# 1-Schematic_Remote1000.net
KiCad netlist of a schematic drawn in EasyEDA
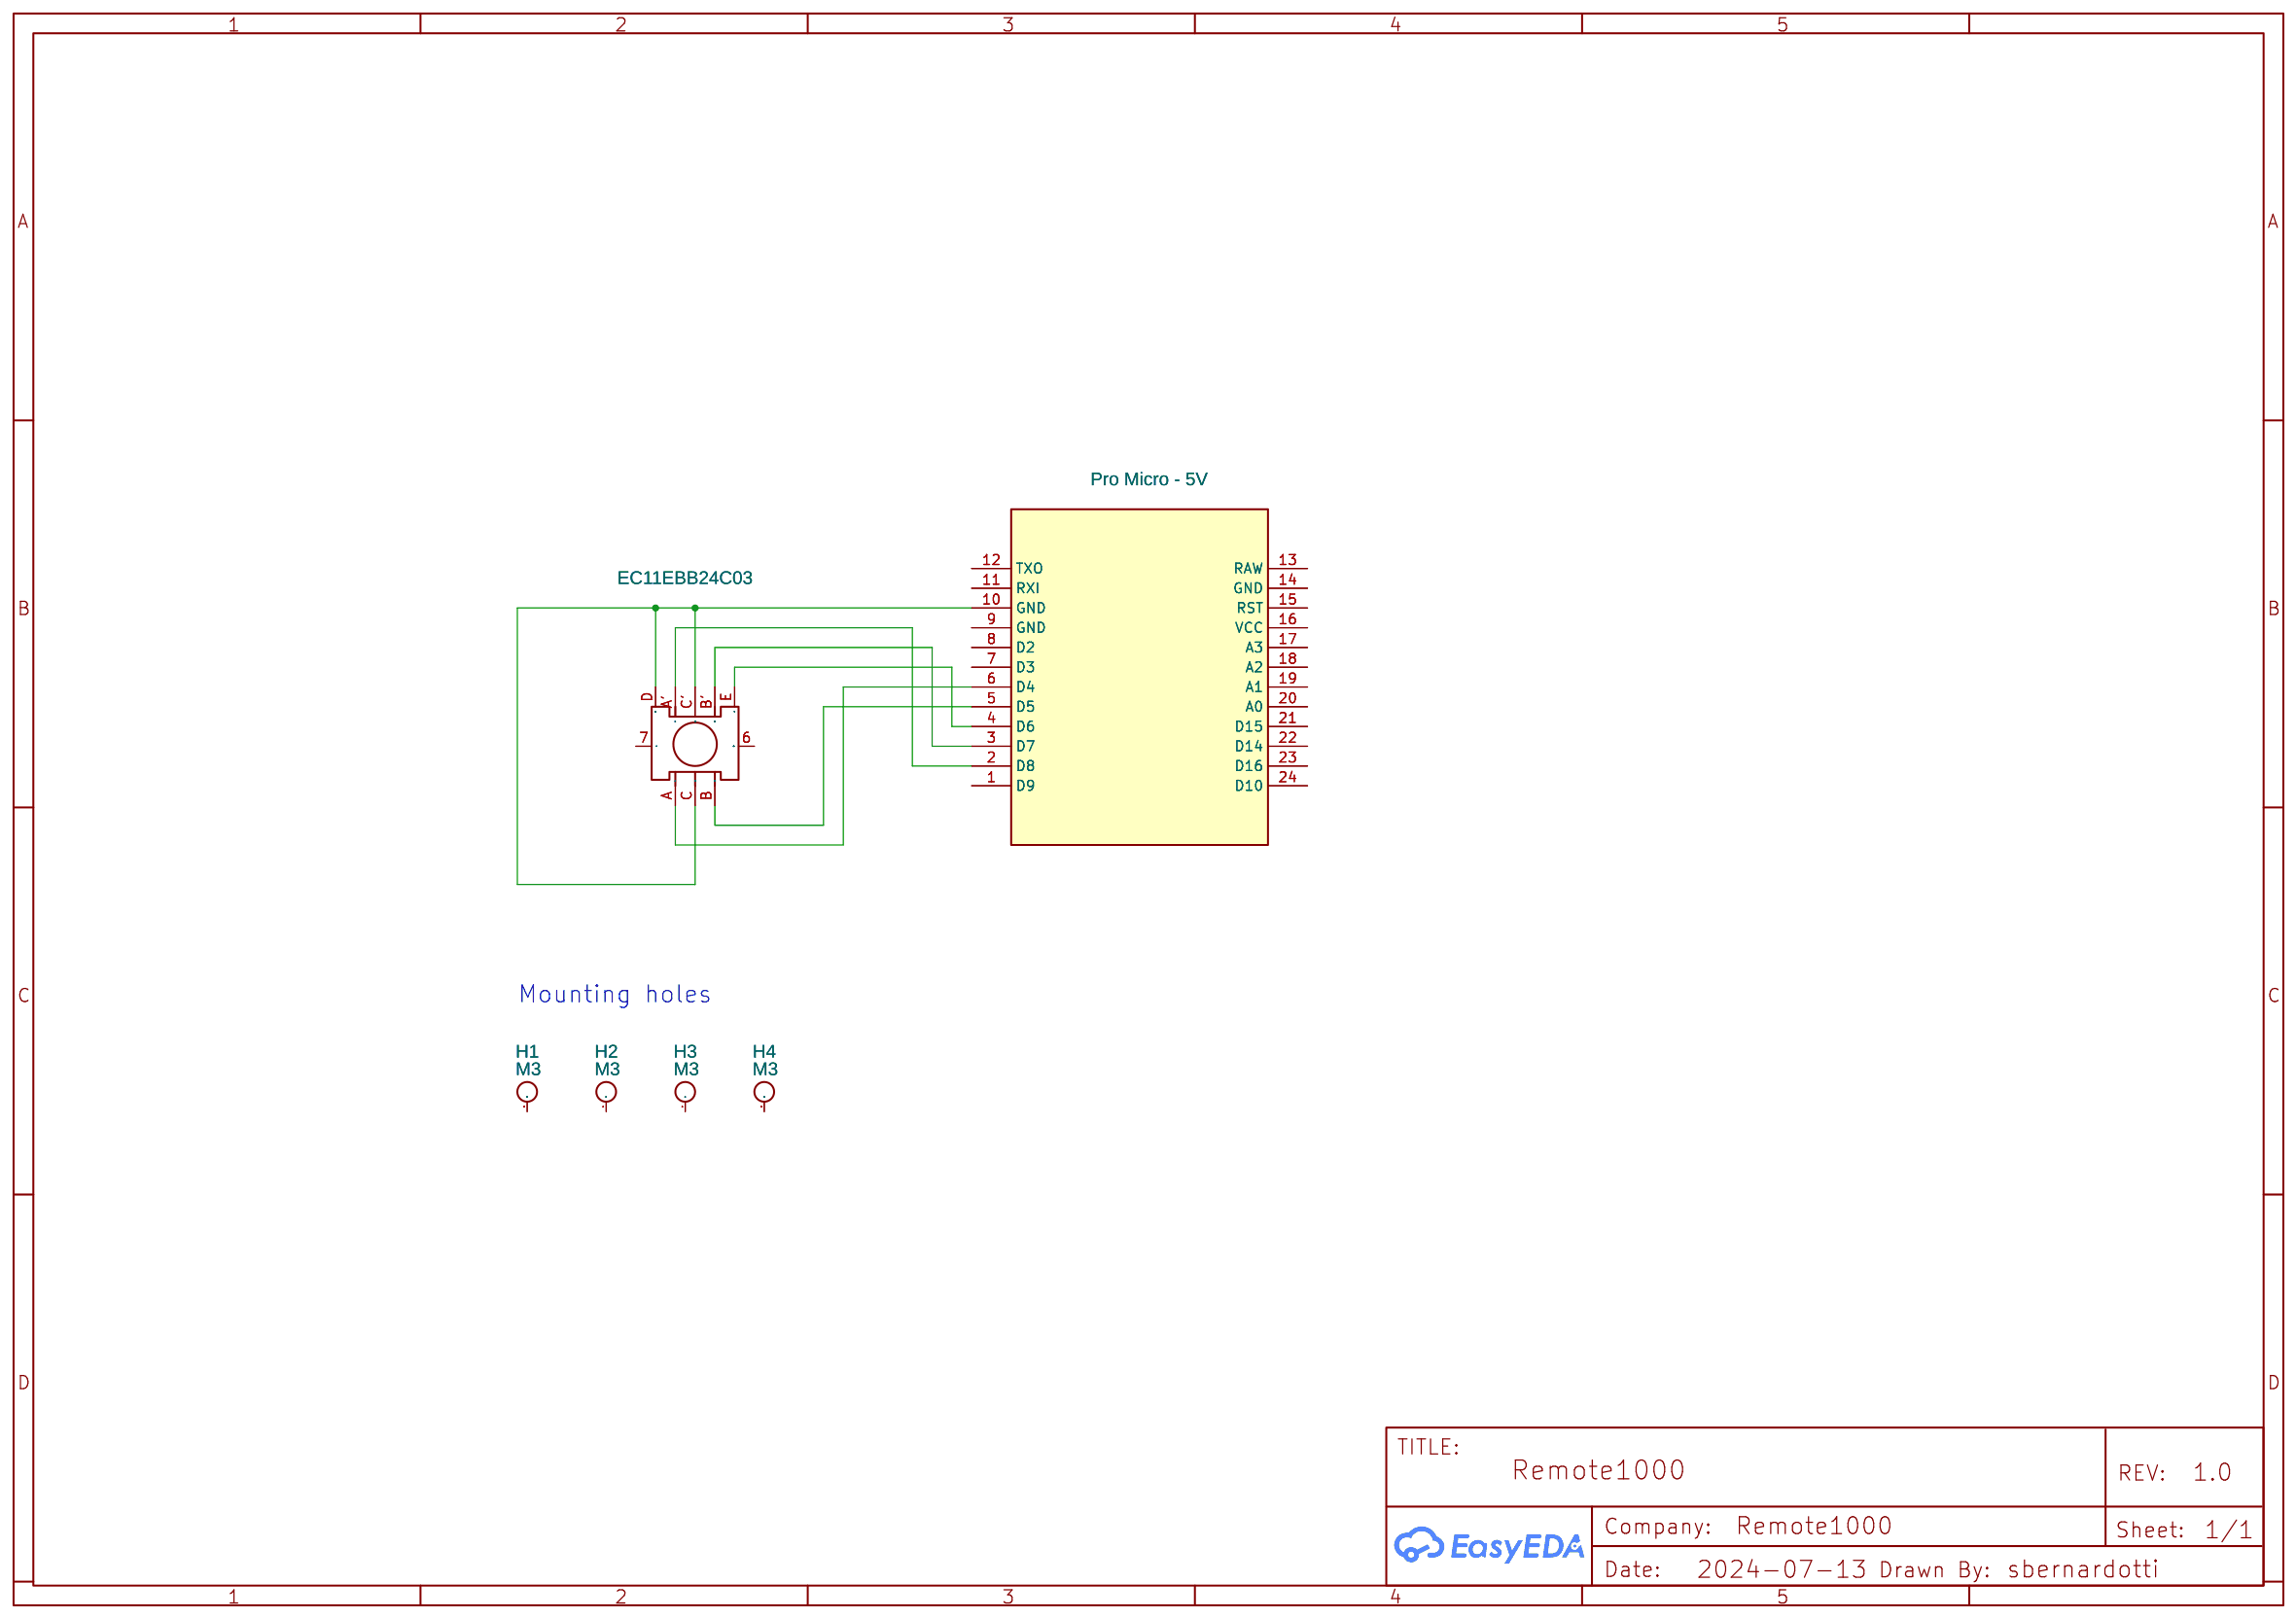
[diagram p0: schematic sheet]

(export (version "E")
  (design (tool "Eeschema 10.0.6"))
  (components
    (comp (ref "H1") (value "M3") (libsource (lib "") (part "HOLE_D3M5_D7M0_PCB_MOUNTING")))
    (comp (ref "H2") (value "M3") (libsource (lib "") (part "HOLE_D3M5_D7M0_PCB_MOUNTING")))
    (comp (ref "H3") (value "M3") (libsource (lib "") (part "HOLE_D3M5_D7M0_PCB_MOUNTING")))
    (comp (ref "H4") (value "M3") (libsource (lib "") (part "HOLE_D3M5_D7M0_PCB_MOUNTING")))
    (comp (ref "P1") (value "Pro Micro - 5V") (libsource (lib "") (part "Pro Micro - 5V")))
    (comp (ref "SW1")
      (value "EC11EBB24C03")
      (fields (field (name "Manufacturer") "ALPSALPINE(阿尔卑斯阿尔派)"))
      (libsource (lib "") (part "EC11EBB24C03"))
    )
  )
  (nets
    (net (code "1") (name "Net-(P1-D4)") (class "Default")
      (node (ref "P1") (pin "6") (pinfunction "D4_6") (pintype "unspecified"))
      (node (ref "SW1") (pin "A") (pinfunction "A_A") (pintype "unspecified"))
    )
    (net (code "2") (name "Net-(P1-D5)") (class "Default")
      (node (ref "P1") (pin "5") (pinfunction "D5_5") (pintype "unspecified"))
      (node (ref "SW1") (pin "B") (pinfunction "B_B") (pintype "unspecified"))
    )
    (net (code "3") (name "Net-(P1-D6)") (class "Default")
      (node (ref "P1") (pin "4") (pinfunction "D6_4") (pintype "unspecified"))
      (node (ref "SW1") (pin "E") (pinfunction "E_E") (pintype "unspecified"))
    )
    (net (code "4") (name "Net-(P1-D7)") (class "Default")
      (node (ref "P1") (pin "3") (pinfunction "D7_3") (pintype "unspecified"))
      (node (ref "SW1") (pin "B'") (pinfunction "B'_B'") (pintype "unspecified"))
    )
    (net (code "5") (name "Net-(P1-D8)") (class "Default")
      (node (ref "P1") (pin "2") (pinfunction "D8_2") (pintype "unspecified"))
      (node (ref "SW1") (pin "A'") (pinfunction "A'_A'") (pintype "unspecified"))
    )
    (net (code "6") (name "Net-(P1-GND-Pad10)") (class "Default")
      (node (ref "P1") (pin "10") (pinfunction "GND_10") (pintype "unspecified"))
      (node (ref "SW1") (pin "C") (pinfunction "C_C") (pintype "unspecified"))
      (node (ref "SW1") (pin "C'") (pinfunction "C'_C'") (pintype "unspecified"))
      (node (ref "SW1") (pin "D") (pinfunction "D_D") (pintype "unspecified"))
    )
    (net (code "7") (name "unconnected-(H1-Pad1)") (class "Default")
      (node (ref "H1") (pin "1") (pinfunction "1_1") (pintype "unspecified"))
    )
    (net (code "8") (name "unconnected-(H2-Pad1)") (class "Default")
      (node (ref "H2") (pin "1") (pinfunction "1_1") (pintype "unspecified"))
    )
    (net (code "9") (name "unconnected-(H3-Pad1)") (class "Default")
      (node (ref "H3") (pin "1") (pinfunction "1_1") (pintype "unspecified"))
    )
    (net (code "10") (name "unconnected-(H4-Pad1)") (class "Default")
      (node (ref "H4") (pin "1") (pinfunction "1_1") (pintype "unspecified"))
    )
    (net (code "11") (name "unconnected-(P1-A0-Pad20)") (class "Default")
      (node (ref "P1") (pin "20") (pinfunction "A0_20") (pintype "unspecified"))
    )
    (net (code "12") (name "unconnected-(P1-A1-Pad19)") (class "Default")
      (node (ref "P1") (pin "19") (pinfunction "A1_19") (pintype "unspecified"))
    )
    (net (code "13") (name "unconnected-(P1-A2-Pad18)") (class "Default")
      (node (ref "P1") (pin "18") (pinfunction "A2_18") (pintype "unspecified"))
    )
    (net (code "14") (name "unconnected-(P1-A3-Pad17)") (class "Default")
      (node (ref "P1") (pin "17") (pinfunction "A3_17") (pintype "unspecified"))
    )
    (net (code "15") (name "unconnected-(P1-D2-Pad8)") (class "Default")
      (node (ref "P1") (pin "8") (pinfunction "D2_8") (pintype "unspecified"))
    )
    (net (code "16") (name "unconnected-(P1-D3-Pad7)") (class "Default")
      (node (ref "P1") (pin "7") (pinfunction "D3_7") (pintype "unspecified"))
    )
    (net (code "17") (name "unconnected-(P1-D9-Pad1)") (class "Default")
      (node (ref "P1") (pin "1") (pinfunction "D9_1") (pintype "unspecified"))
    )
    (net (code "18") (name "unconnected-(P1-D10-Pad24)") (class "Default")
      (node (ref "P1") (pin "24") (pinfunction "D10_24") (pintype "unspecified"))
    )
    (net (code "19") (name "unconnected-(P1-D14-Pad22)") (class "Default")
      (node (ref "P1") (pin "22") (pinfunction "D14_22") (pintype "unspecified"))
    )
    (net (code "20") (name "unconnected-(P1-D15-Pad21)") (class "Default")
      (node (ref "P1") (pin "21") (pinfunction "D15_21") (pintype "unspecified"))
    )
    (net (code "21") (name "unconnected-(P1-D16-Pad23)") (class "Default")
      (node (ref "P1") (pin "23") (pinfunction "D16_23") (pintype "unspecified"))
    )
    (net (code "22") (name "unconnected-(P1-GND-Pad9)") (class "Default")
      (node (ref "P1") (pin "9") (pinfunction "GND_9") (pintype "unspecified"))
    )
    (net (code "23") (name "unconnected-(P1-GND-Pad14)") (class "Default")
      (node (ref "P1") (pin "14") (pinfunction "GND_14") (pintype "unspecified"))
    )
    (net (code "24") (name "unconnected-(P1-RAW-Pad13)") (class "Default")
      (node (ref "P1") (pin "13") (pinfunction "RAW_13") (pintype "unspecified"))
    )
    (net (code "25") (name "unconnected-(P1-RST-Pad15)") (class "Default")
      (node (ref "P1") (pin "15") (pinfunction "RST_15") (pintype "unspecified"))
    )
    (net (code "26") (name "unconnected-(P1-RXI-Pad11)") (class "Default")
      (node (ref "P1") (pin "11") (pinfunction "RXI_11") (pintype "unspecified"))
    )
    (net (code "27") (name "unconnected-(P1-TXO-Pad12)") (class "Default")
      (node (ref "P1") (pin "12") (pinfunction "TXO_12") (pintype "unspecified"))
    )
    (net (code "28") (name "unconnected-(P1-VCC-Pad16)") (class "Default")
      (node (ref "P1") (pin "16") (pinfunction "VCC_16") (pintype "unspecified"))
    )
    (net (code "29") (name "unconnected-(SW1-Pad6)") (class "Default")
      (node (ref "SW1") (pin "6") (pinfunction "6_6") (pintype "unspecified"))
    )
    (net (code "30") (name "unconnected-(SW1-Pad7)") (class "Default")
      (node (ref "SW1") (pin "7") (pinfunction "7_7") (pintype "unspecified"))
    )
  )
)
